# ChannelOutput-x2.net
KiCad netlist of a schematic drawn in EAGLE
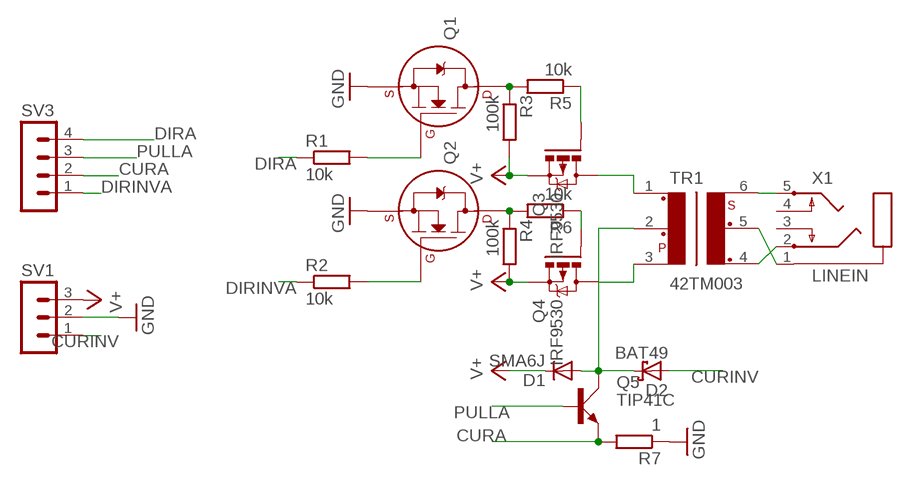
[diagram p0: schematic, sheet 1]
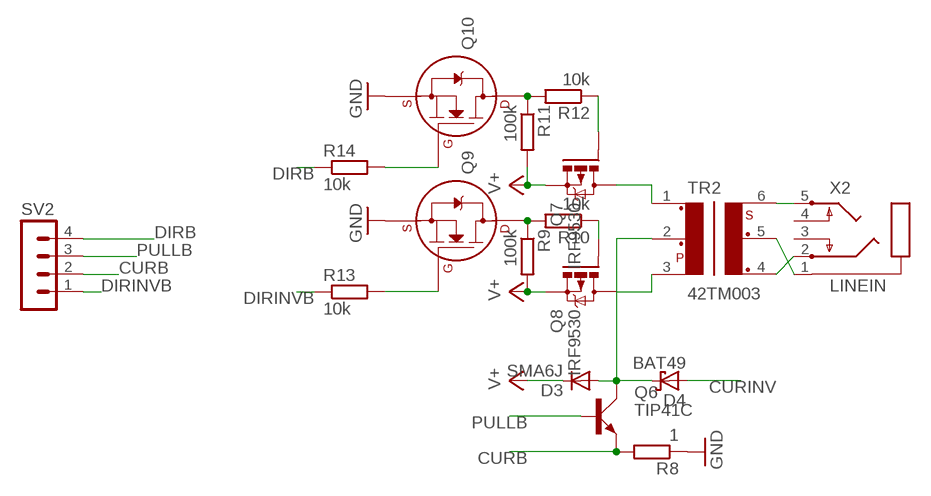
[diagram p1: schematic, sheet 2]

(export (version "E")
  (design (tool "Eeschema 10.0.6"))
  (components
    (comp (ref "D3")
      (value "SMA6J")
      (footprint "eagle-import:DO41-10")
      (libsource (lib "eagle-import") (part "1N4004"))
    )
    (comp (ref "D4")
      (value "BAT49")
      (footprint "eagle-import:DO41-10")
      (libsource (lib "eagle-import") (part "BAT49"))
    )
    (comp (ref "Q6")
      (value "TIP41C")
      (footprint "eagle-import:TO220AV")
      (libsource (lib "eagle-import") (part "TIP41C"))
    )
    (comp (ref "Q7")
      (value "IRF9530")
      (footprint "eagle-import:TO220BV")
      (libsource (lib "eagle-import") (part "IRF9530"))
    )
    (comp (ref "Q8")
      (value "IRF9530")
      (footprint "eagle-import:TO220BV")
      (libsource (lib "eagle-import") (part "IRF9530"))
    )
    (comp (ref "Q9")
      (value "2N7000_TO92")
      (footprint "eagle-import:TO-92")
      (libsource (lib "eagle-import") (part "2N700_TO920"))
    )
    (comp (ref "Q10")
      (value "2N7000_TO92")
      (footprint "eagle-import:TO-92")
      (libsource (lib "eagle-import") (part "2N700_TO920"))
    )
    (comp (ref "R8")
      (value "1")
      (footprint "eagle-import:0207_2V")
      (libsource (lib "eagle-import") (part "R-EU_0207/2V"))
    )
    (comp (ref "R9")
      (value "100k")
      (footprint "eagle-import:0204_5")
      (libsource (lib "eagle-import") (part "R-EU_0204/5"))
    )
    (comp (ref "R10")
      (value "10k")
      (footprint "eagle-import:0207_2V")
      (libsource (lib "eagle-import") (part "R-EU_0207/2V"))
    )
    (comp (ref "R11")
      (value "100k")
      (footprint "eagle-import:0204_5")
      (libsource (lib "eagle-import") (part "R-EU_0204/5"))
    )
    (comp (ref "R12")
      (value "10k")
      (footprint "eagle-import:0207_2V")
      (libsource (lib "eagle-import") (part "R-EU_0207/2V"))
    )
    (comp (ref "R13")
      (value "10k")
      (footprint "eagle-import:0207_2V")
      (libsource (lib "eagle-import") (part "R-EU_0207/2V"))
    )
    (comp (ref "R14")
      (value "10k")
      (footprint "eagle-import:0207_2V")
      (libsource (lib "eagle-import") (part "R-EU_0207/2V"))
    )
    (comp (ref "SV2")
      (value "MA04-1")
      (footprint "eagle-import:MA04-1")
      (libsource (lib "eagle-import") (part "MA04-1"))
    )
    (comp (ref "TR2")
      (value "42TM003")
      (footprint "eagle-import:42TM")
      (libsource (lib "eagle-import") (part "42T?M003"))
    )
    (comp (ref "X2")
      (value "LINEIN")
      (footprint "eagle-import:PG203J")
      (libsource (lib "eagle-import") (part "PG203J"))
    )
    (comp (ref "D1")
      (value "SMA6J")
      (footprint "eagle-import:DO41-10")
      (libsource (lib "eagle-import") (part "1N4004"))
    )
    (comp (ref "D2")
      (value "BAT49")
      (footprint "eagle-import:DO41-10")
      (libsource (lib "eagle-import") (part "BAT49"))
    )
    (comp (ref "Q1")
      (value "2N7000_TO92")
      (footprint "eagle-import:TO-92")
      (libsource (lib "eagle-import") (part "2N700_TO920"))
    )
    (comp (ref "Q2")
      (value "2N7000_TO92")
      (footprint "eagle-import:TO-92")
      (libsource (lib "eagle-import") (part "2N700_TO920"))
    )
    (comp (ref "Q3")
      (value "IRF9530")
      (footprint "eagle-import:TO220BV")
      (libsource (lib "eagle-import") (part "IRF9530"))
    )
    (comp (ref "Q4")
      (value "IRF9530")
      (footprint "eagle-import:TO220BV")
      (libsource (lib "eagle-import") (part "IRF9530"))
    )
    (comp (ref "Q5")
      (value "TIP41C")
      (footprint "eagle-import:TO220AV")
      (libsource (lib "eagle-import") (part "TIP41C"))
    )
    (comp (ref "R1")
      (value "10k")
      (footprint "eagle-import:0207_2V")
      (libsource (lib "eagle-import") (part "R-EU_0207/2V"))
    )
    (comp (ref "R2")
      (value "10k")
      (footprint "eagle-import:0207_2V")
      (libsource (lib "eagle-import") (part "R-EU_0207/2V"))
    )
    (comp (ref "R3")
      (value "100k")
      (footprint "eagle-import:0204_5")
      (libsource (lib "eagle-import") (part "R-EU_0204/5"))
    )
    (comp (ref "R4")
      (value "100k")
      (footprint "eagle-import:0204_5")
      (libsource (lib "eagle-import") (part "R-EU_0204/5"))
    )
    (comp (ref "R5")
      (value "10k")
      (footprint "eagle-import:0207_2V")
      (libsource (lib "eagle-import") (part "R-EU_0207/2V"))
    )
    (comp (ref "R6")
      (value "10k")
      (footprint "eagle-import:0207_2V")
      (libsource (lib "eagle-import") (part "R-EU_0207/2V"))
    )
    (comp (ref "R7")
      (value "1")
      (footprint "eagle-import:0207_2V")
      (libsource (lib "eagle-import") (part "R-EU_0207/2V"))
    )
    (comp (ref "SV1")
      (value "MA03-1")
      (footprint "eagle-import:MA03-1")
      (libsource (lib "eagle-import") (part "MA03-1"))
    )
    (comp (ref "SV3")
      (value "MA04-1")
      (footprint "eagle-import:MA04-1")
      (libsource (lib "eagle-import") (part "MA04-1"))
    )
    (comp (ref "TR1")
      (value "42TM003")
      (footprint "eagle-import:42TM")
      (libsource (lib "eagle-import") (part "42T?M003"))
    )
    (comp (ref "X1")
      (value "LINEIN")
      (footprint "eagle-import:PG203J")
      (libsource (lib "eagle-import") (part "PG203J"))
    )
  )
  (nets
    (net (code "1") (name "CURA") (class "Default")
      (node (ref "Q5") (pin "E") (pinfunction "E_E") (pintype "passive"))
      (node (ref "R7") (pin "2") (pinfunction "2_2") (pintype "passive"))
      (node (ref "SV3") (pin "2") (pinfunction "2_2") (pintype "passive"))
    )
    (net (code "2") (name "CURB") (class "Default")
      (node (ref "Q6") (pin "E") (pinfunction "E_E") (pintype "passive"))
      (node (ref "R8") (pin "2") (pinfunction "2_2") (pintype "passive"))
      (node (ref "SV2") (pin "2") (pinfunction "2_2") (pintype "passive"))
    )
    (net (code "3") (name "CURINV") (class "Default")
      (node (ref "D2") (pin "A") (pinfunction "A_A") (pintype "passive"))
      (node (ref "D4") (pin "A") (pinfunction "A_A") (pintype "passive"))
      (node (ref "SV1") (pin "1") (pinfunction "1_1") (pintype "passive"))
    )
    (net (code "4") (name "DIRA") (class "Default")
      (node (ref "R1") (pin "1") (pinfunction "1_1") (pintype "passive"))
      (node (ref "SV3") (pin "4") (pinfunction "4_4") (pintype "passive"))
    )
    (net (code "5") (name "DIRB") (class "Default")
      (node (ref "R14") (pin "1") (pinfunction "1_1") (pintype "passive"))
      (node (ref "SV2") (pin "4") (pinfunction "4_4") (pintype "passive"))
    )
    (net (code "6") (name "DIRINVA") (class "Default")
      (node (ref "R2") (pin "1") (pinfunction "1_1") (pintype "passive"))
      (node (ref "SV3") (pin "1") (pinfunction "1_1") (pintype "passive"))
    )
    (net (code "7") (name "DIRINVB") (class "Default")
      (node (ref "R13") (pin "1") (pinfunction "1_1") (pintype "passive"))
      (node (ref "SV2") (pin "1") (pinfunction "1_1") (pintype "passive"))
    )
    (net (code "8") (name "GND") (class "Default")
      (node (ref "Q1") (pin "1") (pinfunction "S_1") (pintype "bidirectional"))
      (node (ref "Q10") (pin "1") (pinfunction "S_1") (pintype "bidirectional"))
      (node (ref "Q2") (pin "1") (pinfunction "S_1") (pintype "bidirectional"))
      (node (ref "Q9") (pin "1") (pinfunction "S_1") (pintype "bidirectional"))
      (node (ref "R7") (pin "1") (pinfunction "1_1") (pintype "passive"))
      (node (ref "R8") (pin "1") (pinfunction "1_1") (pintype "passive"))
      (node (ref "SV1") (pin "2") (pinfunction "2_2") (pintype "passive"))
    )
    (net (code "9") (name "Net-(D1-PadA)") (class "Default")
      (node (ref "D1") (pin "A") (pinfunction "A_A") (pintype "passive"))
      (node (ref "D2") (pin "C") (pinfunction "C_C") (pintype "passive"))
      (node (ref "Q5") (pin "C") (pinfunction "C_C") (pintype "passive"))
      (node (ref "TR1") (pin "2") (pinfunction "2_2") (pintype "passive"))
    )
    (net (code "10") (name "Net-(D3-PadA)") (class "Default")
      (node (ref "D3") (pin "A") (pinfunction "A_A") (pintype "passive"))
      (node (ref "D4") (pin "C") (pinfunction "C_C") (pintype "passive"))
      (node (ref "Q6") (pin "C") (pinfunction "C_C") (pintype "passive"))
      (node (ref "TR2") (pin "2") (pinfunction "2_2") (pintype "passive"))
    )
    (net (code "11") (name "Net-(Q1-D)") (class "Default")
      (node (ref "Q1") (pin "3") (pinfunction "D_3") (pintype "bidirectional"))
      (node (ref "R3") (pin "1") (pinfunction "1_1") (pintype "passive"))
      (node (ref "R5") (pin "2") (pinfunction "2_2") (pintype "passive"))
    )
    (net (code "12") (name "Net-(Q1-G)") (class "Default")
      (node (ref "Q1") (pin "2") (pinfunction "G_2") (pintype "tri_state"))
      (node (ref "R1") (pin "2") (pinfunction "2_2") (pintype "passive"))
    )
    (net (code "13") (name "Net-(Q2-D)") (class "Default")
      (node (ref "Q2") (pin "3") (pinfunction "D_3") (pintype "bidirectional"))
      (node (ref "R4") (pin "1") (pinfunction "1_1") (pintype "passive"))
      (node (ref "R6") (pin "2") (pinfunction "2_2") (pintype "passive"))
    )
    (net (code "14") (name "Net-(Q2-G)") (class "Default")
      (node (ref "Q2") (pin "2") (pinfunction "G_2") (pintype "tri_state"))
      (node (ref "R2") (pin "2") (pinfunction "2_2") (pintype "passive"))
    )
    (net (code "15") (name "Net-(Q3-PadD)") (class "Default")
      (node (ref "Q3") (pin "D") (pinfunction "D_D") (pintype "passive"))
      (node (ref "TR1") (pin "1") (pinfunction "1_1") (pintype "passive"))
    )
    (net (code "16") (name "Net-(Q3-PadG)") (class "Default")
      (node (ref "Q3") (pin "G") (pinfunction "G_G") (pintype "passive"))
      (node (ref "R5") (pin "1") (pinfunction "1_1") (pintype "passive"))
    )
    (net (code "17") (name "Net-(Q4-PadD)") (class "Default")
      (node (ref "Q4") (pin "D") (pinfunction "D_D") (pintype "passive"))
      (node (ref "TR1") (pin "3") (pinfunction "3_3") (pintype "passive"))
    )
    (net (code "18") (name "Net-(Q4-PadG)") (class "Default")
      (node (ref "Q4") (pin "G") (pinfunction "G_G") (pintype "passive"))
      (node (ref "R6") (pin "1") (pinfunction "1_1") (pintype "passive"))
    )
    (net (code "19") (name "Net-(Q7-PadD)") (class "Default")
      (node (ref "Q7") (pin "D") (pinfunction "D_D") (pintype "passive"))
      (node (ref "TR2") (pin "1") (pinfunction "1_1") (pintype "passive"))
    )
    (net (code "20") (name "Net-(Q7-PadG)") (class "Default")
      (node (ref "Q7") (pin "G") (pinfunction "G_G") (pintype "passive"))
      (node (ref "R12") (pin "1") (pinfunction "1_1") (pintype "passive"))
    )
    (net (code "21") (name "Net-(Q8-PadD)") (class "Default")
      (node (ref "Q8") (pin "D") (pinfunction "D_D") (pintype "passive"))
      (node (ref "TR2") (pin "3") (pinfunction "3_3") (pintype "passive"))
    )
    (net (code "22") (name "Net-(Q8-PadG)") (class "Default")
      (node (ref "Q8") (pin "G") (pinfunction "G_G") (pintype "passive"))
      (node (ref "R10") (pin "1") (pinfunction "1_1") (pintype "passive"))
    )
    (net (code "23") (name "Net-(Q9-D)") (class "Default")
      (node (ref "Q9") (pin "3") (pinfunction "D_3") (pintype "bidirectional"))
      (node (ref "R10") (pin "2") (pinfunction "2_2") (pintype "passive"))
      (node (ref "R9") (pin "1") (pinfunction "1_1") (pintype "passive"))
    )
    (net (code "24") (name "Net-(Q9-G)") (class "Default")
      (node (ref "Q9") (pin "2") (pinfunction "G_2") (pintype "tri_state"))
      (node (ref "R13") (pin "2") (pinfunction "2_2") (pintype "passive"))
    )
    (net (code "25") (name "Net-(Q10-D)") (class "Default")
      (node (ref "Q10") (pin "3") (pinfunction "D_3") (pintype "bidirectional"))
      (node (ref "R11") (pin "1") (pinfunction "1_1") (pintype "passive"))
      (node (ref "R12") (pin "2") (pinfunction "2_2") (pintype "passive"))
    )
    (net (code "26") (name "Net-(Q10-G)") (class "Default")
      (node (ref "Q10") (pin "2") (pinfunction "G_2") (pintype "tri_state"))
      (node (ref "R14") (pin "2") (pinfunction "2_2") (pintype "passive"))
    )
    (net (code "27") (name "Net-(TR1-Pad4)") (class "Default")
      (node (ref "TR1") (pin "4") (pinfunction "4_4") (pintype "passive"))
      (node (ref "X1") (pin "2") (pinfunction "2_2") (pintype "passive"))
    )
    (net (code "28") (name "Net-(TR1-Pad5)") (class "Default")
      (node (ref "TR1") (pin "5") (pinfunction "5_5") (pintype "passive"))
      (node (ref "X1") (pin "1") (pinfunction "1_1") (pintype "passive"))
    )
    (net (code "29") (name "Net-(TR1-Pad6)") (class "Default")
      (node (ref "TR1") (pin "6") (pinfunction "6_6") (pintype "passive"))
      (node (ref "X1") (pin "5") (pinfunction "5_5") (pintype "passive"))
    )
    (net (code "30") (name "Net-(TR2-Pad4)") (class "Default")
      (node (ref "TR2") (pin "4") (pinfunction "4_4") (pintype "passive"))
      (node (ref "X2") (pin "2") (pinfunction "2_2") (pintype "passive"))
    )
    (net (code "31") (name "Net-(TR2-Pad5)") (class "Default")
      (node (ref "TR2") (pin "5") (pinfunction "5_5") (pintype "passive"))
      (node (ref "X2") (pin "1") (pinfunction "1_1") (pintype "passive"))
    )
    (net (code "32") (name "Net-(TR2-Pad6)") (class "Default")
      (node (ref "TR2") (pin "6") (pinfunction "6_6") (pintype "passive"))
      (node (ref "X2") (pin "5") (pinfunction "5_5") (pintype "passive"))
    )
    (net (code "33") (name "PULLA") (class "Default")
      (node (ref "Q5") (pin "B") (pinfunction "B_B") (pintype "passive"))
      (node (ref "SV3") (pin "3") (pinfunction "3_3") (pintype "passive"))
    )
    (net (code "34") (name "PULLB") (class "Default")
      (node (ref "Q6") (pin "B") (pinfunction "B_B") (pintype "passive"))
      (node (ref "SV2") (pin "3") (pinfunction "3_3") (pintype "passive"))
    )
    (net (code "35") (name "V+") (class "Default")
      (node (ref "D1") (pin "C") (pinfunction "C_C") (pintype "passive"))
      (node (ref "D3") (pin "C") (pinfunction "C_C") (pintype "passive"))
      (node (ref "Q3") (pin "S") (pinfunction "S_S") (pintype "passive"))
      (node (ref "Q4") (pin "S") (pinfunction "S_S") (pintype "passive"))
      (node (ref "Q7") (pin "S") (pinfunction "S_S") (pintype "passive"))
      (node (ref "Q8") (pin "S") (pinfunction "S_S") (pintype "passive"))
      (node (ref "R11") (pin "2") (pinfunction "2_2") (pintype "passive"))
      (node (ref "R3") (pin "2") (pinfunction "2_2") (pintype "passive"))
      (node (ref "R4") (pin "2") (pinfunction "2_2") (pintype "passive"))
      (node (ref "R9") (pin "2") (pinfunction "2_2") (pintype "passive"))
      (node (ref "SV1") (pin "3") (pinfunction "3_3") (pintype "passive"))
    )
    (net (code "36") (name "unconnected-(X1-Pad3)") (class "Default")
      (node (ref "X1") (pin "3") (pinfunction "3_3") (pintype "passive"))
    )
    (net (code "37") (name "unconnected-(X1-Pad4)") (class "Default")
      (node (ref "X1") (pin "4") (pinfunction "4_4") (pintype "passive"))
    )
    (net (code "38") (name "unconnected-(X2-Pad3)") (class "Default")
      (node (ref "X2") (pin "3") (pinfunction "3_3") (pintype "passive"))
    )
    (net (code "39") (name "unconnected-(X2-Pad4)") (class "Default")
      (node (ref "X2") (pin "4") (pinfunction "4_4") (pintype "passive"))
    )
  )
)
